# bicyclelab-charger-3.net
KiCad netlist of a schematic drawn in EAGLE
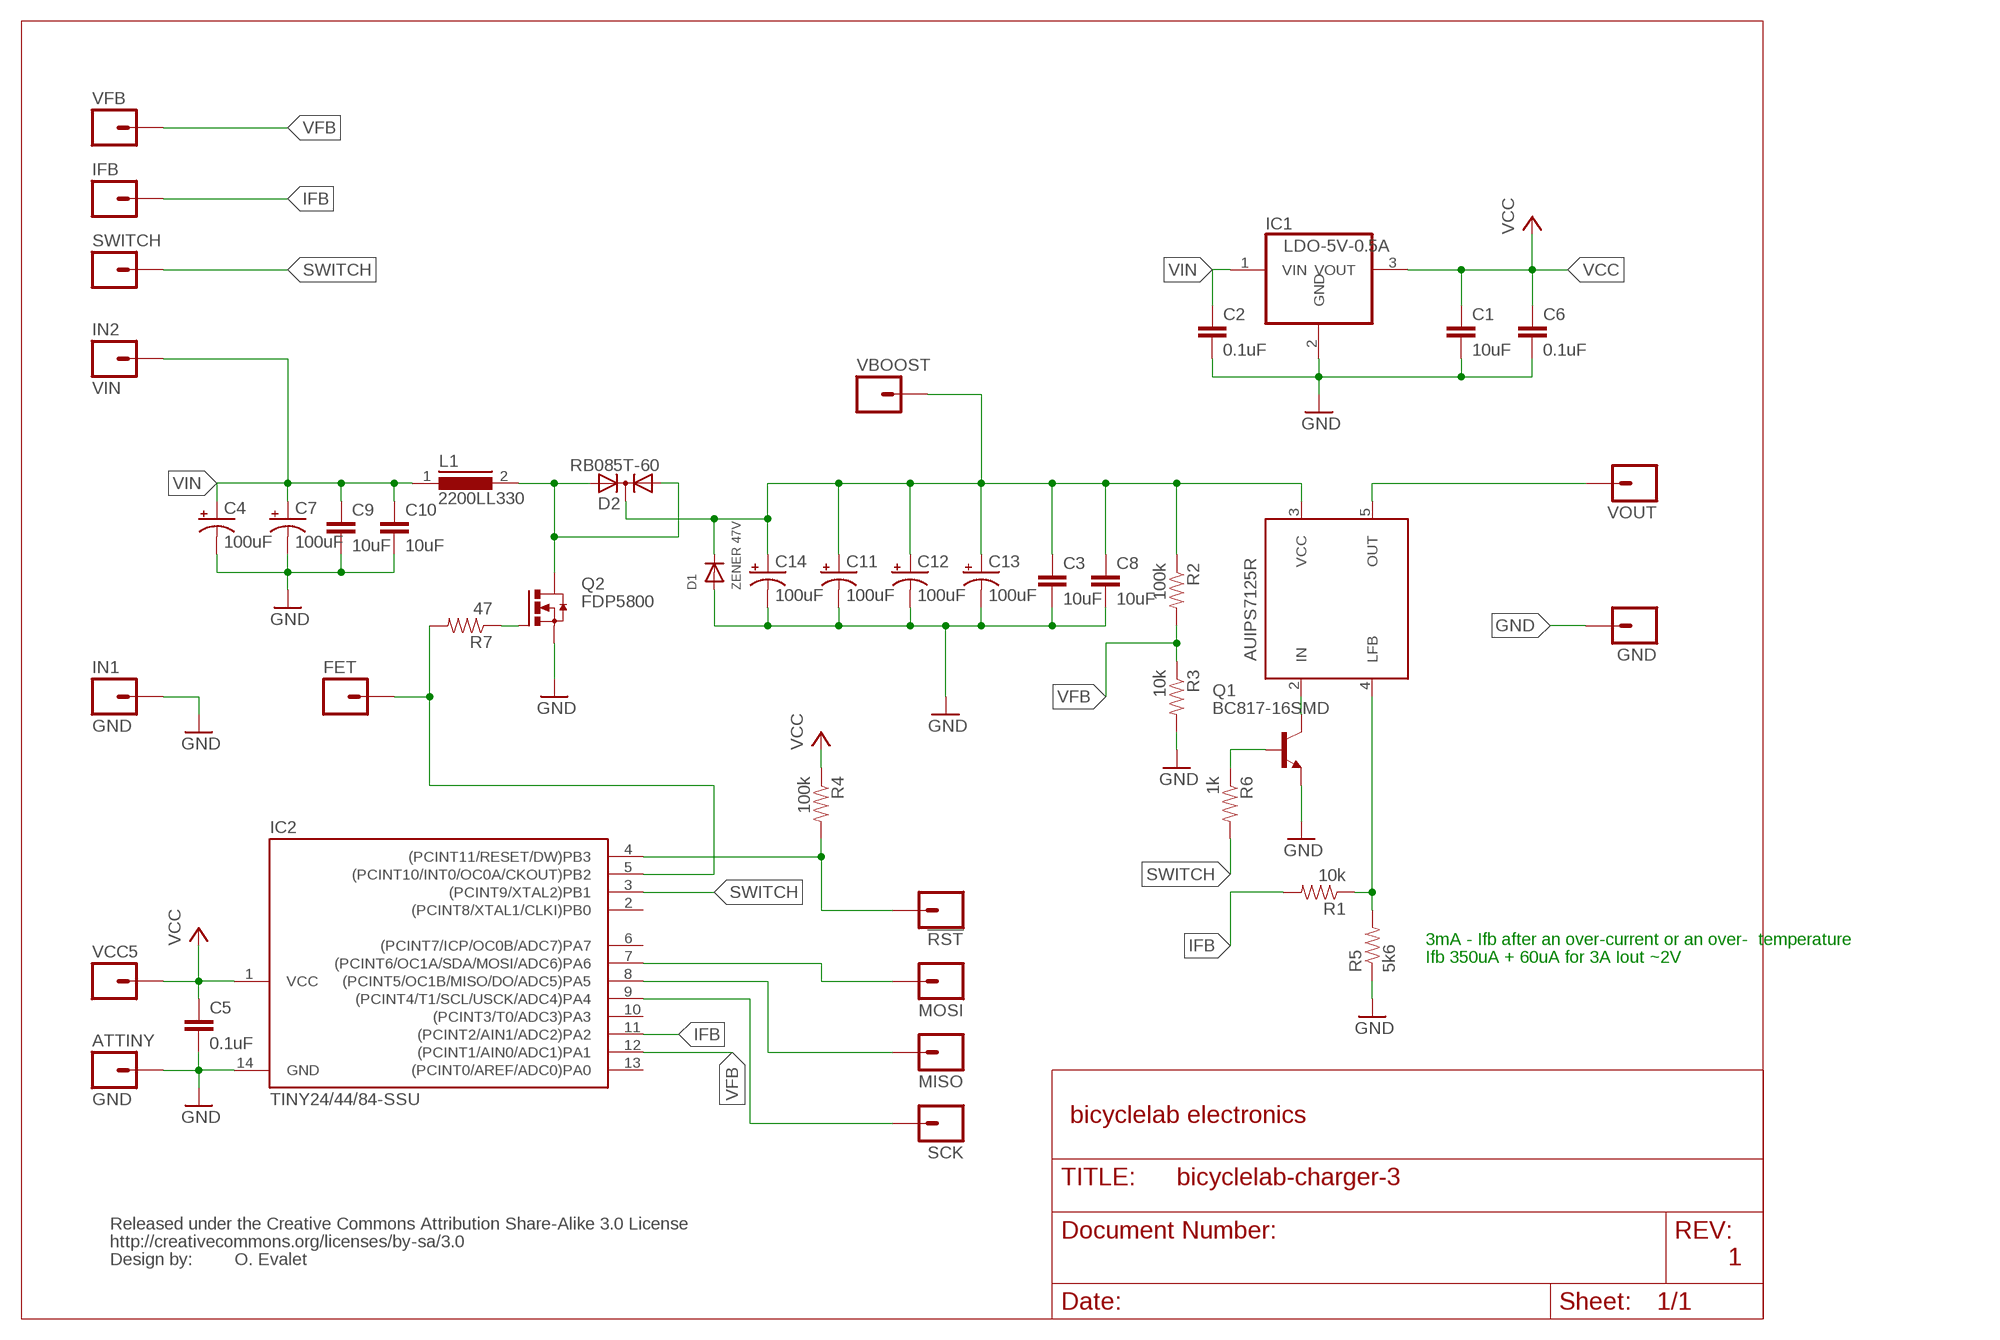
[diagram p0: schematic, sheet 1]

(export (version "E")
  (design (tool "Eeschema 10.0.6"))
  (components
    (comp (ref "!RST")
      (value "M01SMDNS")
      (footprint "eagle-import:1X01NS")
      (libsource (lib "eagle-import") (part "M01SMDNS"))
    )
    (comp (ref "ATTINY")
      (value "GND")
      (footprint "eagle-import:1X01NS")
      (libsource (lib "eagle-import") (part "M01SMDNS"))
    )
    (comp (ref "C1")
      (value "10uF")
      (footprint "eagle-import:1210")
      (libsource (lib "eagle-import") (part "CAP1210"))
    )
    (comp (ref "C2")
      (value "0.1uF")
      (footprint "eagle-import:0805")
      (libsource (lib "eagle-import") (part "CAP0805"))
    )
    (comp (ref "C3")
      (value "10uF")
      (footprint "eagle-import:1210")
      (libsource (lib "eagle-import") (part "CAP1210"))
    )
    (comp (ref "C4")
      (value "100uF")
      (footprint "eagle-import:PANASONIC_D")
      (libsource (lib "eagle-import") (part "CPOL-USD"))
    )
    (comp (ref "C5")
      (value "0.1uF")
      (footprint "eagle-import:0805")
      (libsource (lib "eagle-import") (part "CAP0805"))
    )
    (comp (ref "C6")
      (value "0.1uF")
      (footprint "eagle-import:0805")
      (libsource (lib "eagle-import") (part "CAP0805"))
    )
    (comp (ref "C7")
      (value "100uF")
      (footprint "eagle-import:PANASONIC_D")
      (libsource (lib "eagle-import") (part "CPOL-USD"))
    )
    (comp (ref "C8")
      (value "10uF")
      (footprint "eagle-import:1210")
      (libsource (lib "eagle-import") (part "CAP1210"))
    )
    (comp (ref "C9")
      (value "10uF")
      (footprint "eagle-import:1210")
      (libsource (lib "eagle-import") (part "CAP1210"))
    )
    (comp (ref "C10")
      (value "10uF")
      (footprint "eagle-import:1210")
      (libsource (lib "eagle-import") (part "CAP1210"))
    )
    (comp (ref "C11")
      (value "100uF")
      (footprint "eagle-import:PANASONIC_D")
      (libsource (lib "eagle-import") (part "CPOL-USD"))
    )
    (comp (ref "C12")
      (value "100uF")
      (footprint "eagle-import:PANASONIC_D")
      (libsource (lib "eagle-import") (part "CPOL-USD"))
    )
    (comp (ref "C13")
      (value "100uF")
      (footprint "eagle-import:PANASONIC_D")
      (libsource (lib "eagle-import") (part "CPOL-USD"))
    )
    (comp (ref "C14")
      (value "100uF")
      (footprint "eagle-import:PANASONIC_D")
      (libsource (lib "eagle-import") (part "CPOL-USD"))
    )
    (comp (ref "D1")
      (value "ZENER 47V")
      (footprint "eagle-import:SOD-123")
      (libsource (lib "eagle-import") (part "DIODESOD-123"))
    )
    (comp (ref "D2")
      (value "RB085T-60")
      (footprint "eagle-import:TO220AB")
      (libsource (lib "eagle-import") (part "DIODE-2AC|CATO220H"))
    )
    (comp (ref "FET")
      (value "M01SMDNS")
      (footprint "eagle-import:1X01NS")
      (libsource (lib "eagle-import") (part "M01SMDNS"))
    )
    (comp (ref "GND")
      (value "M01SMDNS")
      (footprint "eagle-import:1X01NS")
      (libsource (lib "eagle-import") (part "M01SMDNS"))
    )
    (comp (ref "IC1")
      (value "LDO-5V-0.5A")
      (footprint "eagle-import:SOT223")
      (libsource (lib "eagle-import") (part "LDO-5V-0.5A"))
    )
    (comp (ref "IC2")
      (value "TINY24/44/84-SSU")
      (footprint "eagle-import:SOIC14")
      (libsource (lib "eagle-import") (part "TINY24/44/84-SSU"))
    )
    (comp (ref "IFB")
      (value "M01SMDNS")
      (footprint "eagle-import:1X01NS")
      (libsource (lib "eagle-import") (part "M01SMDNS"))
    )
    (comp (ref "IN1")
      (value "GND")
      (footprint "eagle-import:1X01NS")
      (libsource (lib "eagle-import") (part "M01SMDNS"))
    )
    (comp (ref "IN2")
      (value "VIN")
      (footprint "eagle-import:1X01")
      (libsource (lib "eagle-import") (part "M01PTH"))
    )
    (comp (ref "L1")
      (value "2200LL330")
      (footprint "eagle-import:2200LL")
      (libsource (lib "eagle-import") (part "2200LL"))
    )
    (comp (ref "MISO")
      (value "M01SMDNS")
      (footprint "eagle-import:1X01NS")
      (libsource (lib "eagle-import") (part "M01SMDNS"))
    )
    (comp (ref "MOSI")
      (value "M01SMDNS")
      (footprint "eagle-import:1X01NS")
      (libsource (lib "eagle-import") (part "M01SMDNS"))
    )
    (comp (ref "Q1")
      (value "BC817-16SMD")
      (footprint "eagle-import:SOT23-BEC")
      (libsource (lib "eagle-import") (part "BC817SMD-16"))
    )
    (comp (ref "Q2")
      (value "FDP5800")
      (footprint "eagle-import:TO220AH")
      (libsource (lib "eagle-import") (part "IRF3704"))
    )
    (comp (ref "R1")
      (value "10k")
      (footprint "eagle-import:0805")
      (libsource (lib "eagle-import") (part "RESISTOR"))
    )
    (comp (ref "R2")
      (value "100k")
      (footprint "eagle-import:0805")
      (libsource (lib "eagle-import") (part "RESISTOR"))
    )
    (comp (ref "R3")
      (value "10k")
      (footprint "eagle-import:0805")
      (libsource (lib "eagle-import") (part "RESISTOR"))
    )
    (comp (ref "R4")
      (value "100k")
      (footprint "eagle-import:0805")
      (libsource (lib "eagle-import") (part "RESISTOR"))
    )
    (comp (ref "R5")
      (value "5k6")
      (footprint "eagle-import:0805")
      (libsource (lib "eagle-import") (part "RESISTOR"))
    )
    (comp (ref "R6")
      (value "1k")
      (footprint "eagle-import:0805")
      (libsource (lib "eagle-import") (part "RESISTOR"))
    )
    (comp (ref "R7")
      (value "47")
      (footprint "eagle-import:0805")
      (libsource (lib "eagle-import") (part "RESISTOR"))
    )
    (comp (ref "SCK")
      (value "M01SMDNS")
      (footprint "eagle-import:1X01NS")
      (libsource (lib "eagle-import") (part "M01SMDNS"))
    )
    (comp (ref "SWITCH")
      (value "M01SMDNS")
      (footprint "eagle-import:1X01NS")
      (libsource (lib "eagle-import") (part "M01SMDNS"))
    )
    (comp (ref "U$5")
      (value "CREATIVE_COMMONS")
      (footprint "eagle-import:CREATIVE_COMMONS")
      (libsource (lib "eagle-import") (part "CREATIVE_COMMONS"))
    )
    (comp (ref "U$8")
      (value "AUIPS7125R")
      (footprint "eagle-import:DPAK-5")
      (libsource (lib "eagle-import") (part "AUIPS7125R"))
    )
    (comp (ref "VBOOST")
      (value "M01SMDNS")
      (footprint "eagle-import:1X01NS")
      (libsource (lib "eagle-import") (part "M01SMDNS"))
    )
    (comp (ref "VCC5")
      (value "M01PTH")
      (footprint "eagle-import:1X01")
      (libsource (lib "eagle-import") (part "M01PTH"))
    )
    (comp (ref "VFB")
      (value "M01SMDNS")
      (footprint "eagle-import:1X01NS")
      (libsource (lib "eagle-import") (part "M01SMDNS"))
    )
    (comp (ref "VOUT")
      (value "M01PTH")
      (footprint "eagle-import:1X01")
      (libsource (lib "eagle-import") (part "M01PTH"))
    )
  )
  (nets
    (net (code "1") (name "GND") (class "Default")
      (node (ref "ATTINY") (pin "1") (pinfunction "1_1") (pintype "passive"))
      (node (ref "C1") (pin "2") (pinfunction "2_2") (pintype "passive"))
      (node (ref "C10") (pin "2") (pinfunction "2_2") (pintype "passive"))
      (node (ref "C11") (pin "-") (pinfunction "-_-") (pintype "passive"))
      (node (ref "C12") (pin "-") (pinfunction "-_-") (pintype "passive"))
      (node (ref "C13") (pin "-") (pinfunction "-_-") (pintype "passive"))
      (node (ref "C14") (pin "-") (pinfunction "-_-") (pintype "passive"))
      (node (ref "C2") (pin "2") (pinfunction "2_2") (pintype "passive"))
      (node (ref "C3") (pin "2") (pinfunction "2_2") (pintype "passive"))
      (node (ref "C4") (pin "-") (pinfunction "-_-") (pintype "passive"))
      (node (ref "C5") (pin "2") (pinfunction "2_2") (pintype "passive"))
      (node (ref "C6") (pin "2") (pinfunction "2_2") (pintype "passive"))
      (node (ref "C7") (pin "-") (pinfunction "-_-") (pintype "passive"))
      (node (ref "C8") (pin "2") (pinfunction "2_2") (pintype "passive"))
      (node (ref "C9") (pin "2") (pinfunction "2_2") (pintype "passive"))
      (node (ref "D1") (pin "A") (pinfunction "A_A") (pintype "passive"))
      (node (ref "GND") (pin "1") (pinfunction "1_1") (pintype "passive"))
      (node (ref "IC1") (pin "2") (pinfunction "GND_2") (pintype "power_in"))
      (node (ref "IC2") (pin "14") (pinfunction "GND_14") (pintype "power_in"))
      (node (ref "IN1") (pin "1") (pinfunction "1_1") (pintype "passive"))
      (node (ref "Q1") (pin "E") (pinfunction "E_E") (pintype "passive"))
      (node (ref "Q2") (pin "E") (pinfunction "S_E") (pintype "passive"))
      (node (ref "R3") (pin "2") (pinfunction "2_2") (pintype "passive"))
      (node (ref "R5") (pin "1") (pinfunction "1_1") (pintype "passive"))
    )
    (net (code "2") (name "IFB") (class "Default")
      (node (ref "IC2") (pin "11") (pinfunction "(PCINT2/AIN1/ADC2)PA2_11") (pintype "bidirectional"))
      (node (ref "IFB") (pin "1") (pinfunction "1_1") (pintype "passive"))
      (node (ref "R1") (pin "2") (pinfunction "2_2") (pintype "passive"))
    )
    (net (code "3") (name "Net-(IC2-(PCINT4{slash}T1{slash}SCL{slash}USCK{slash}ADC4)PA4)") (class "Default")
      (node (ref "IC2") (pin "9") (pinfunction "(PCINT4/T1/SCL/USCK/ADC4)PA4_9") (pintype "bidirectional"))
      (node (ref "SCK") (pin "1") (pinfunction "1_1") (pintype "passive"))
    )
    (net (code "4") (name "Net-(IC2-(PCINT5{slash}OC1B{slash}MISO{slash}DO{slash}ADC5)PA5)") (class "Default")
      (node (ref "IC2") (pin "8") (pinfunction "(PCINT5/OC1B/MISO/DO/ADC5)PA5_8") (pintype "bidirectional"))
      (node (ref "MISO") (pin "1") (pinfunction "1_1") (pintype "passive"))
    )
    (net (code "5") (name "Net-(IC2-(PCINT6{slash}OC1A{slash}SDA{slash}MOSI{slash}ADC6)PA6)") (class "Default")
      (node (ref "IC2") (pin "7") (pinfunction "(PCINT6/OC1A/SDA/MOSI/ADC6)PA6_7") (pintype "bidirectional"))
      (node (ref "MOSI") (pin "1") (pinfunction "1_1") (pintype "passive"))
    )
    (net (code "6") (name "Net-(IC2-(PCINT10{slash}INT0{slash}OC0A{slash}CKOUT)PB2)") (class "Default")
      (node (ref "FET") (pin "1") (pinfunction "1_1") (pintype "passive"))
      (node (ref "IC2") (pin "5") (pinfunction "(PCINT10/INT0/OC0A/CKOUT)PB2_5") (pintype "bidirectional"))
      (node (ref "R7") (pin "2") (pinfunction "2_2") (pintype "passive"))
    )
    (net (code "7") (name "Net-(IC2-(PCINT11{slash}RESET{slash}DW)PB3)") (class "Default")
      (node (ref "!RST") (pin "1") (pinfunction "1_1") (pintype "passive"))
      (node (ref "IC2") (pin "4") (pinfunction "(PCINT11/RESET/DW)PB3_4") (pintype "bidirectional"))
      (node (ref "R4") (pin "2") (pinfunction "2_2") (pintype "passive"))
    )
    (net (code "8") (name "Net-(Q1-PadB)") (class "Default")
      (node (ref "Q1") (pin "B") (pinfunction "B_B") (pintype "passive"))
      (node (ref "R6") (pin "1") (pinfunction "1_1") (pintype "passive"))
    )
    (net (code "9") (name "Net-(Q2-D)") (class "Default")
      (node (ref "D2") (pin "A1") (pinfunction "A1_A1") (pintype "passive"))
      (node (ref "D2") (pin "A2") (pinfunction "A2_A2") (pintype "passive"))
      (node (ref "L1") (pin "2") (pinfunction "2_2") (pintype "passive"))
      (node (ref "Q2") (pin "C") (pinfunction "D_C") (pintype "passive"))
    )
    (net (code "10") (name "Net-(Q2-G)") (class "Default")
      (node (ref "Q2") (pin "B") (pinfunction "G_B") (pintype "passive"))
      (node (ref "R7") (pin "1") (pinfunction "1_1") (pintype "passive"))
    )
    (net (code "11") (name "Net-(U$8-IN)") (class "Default")
      (node (ref "Q1") (pin "C") (pinfunction "C_C") (pintype "passive"))
      (node (ref "U$8") (pin "2") (pinfunction "IN_2") (pintype "input"))
    )
    (net (code "12") (name "Net-(U$8-LFB)") (class "Default")
      (node (ref "R1") (pin "1") (pinfunction "1_1") (pintype "passive"))
      (node (ref "R5") (pin "2") (pinfunction "2_2") (pintype "passive"))
      (node (ref "U$8") (pin "4") (pinfunction "LFB_4") (pintype "output"))
    )
    (net (code "13") (name "Net-(U$8-OUT)") (class "Default")
      (node (ref "U$8") (pin "5") (pinfunction "OUT_5") (pintype "output"))
      (node (ref "VOUT") (pin "1") (pinfunction "1_1") (pintype "passive"))
    )
    (net (code "14") (name "Net-(U$8-VCC)") (class "Default")
      (node (ref "C11") (pin "+") (pinfunction "+_+") (pintype "passive"))
      (node (ref "C12") (pin "+") (pinfunction "+_+") (pintype "passive"))
      (node (ref "C13") (pin "+") (pinfunction "+_+") (pintype "passive"))
      (node (ref "C14") (pin "+") (pinfunction "+_+") (pintype "passive"))
      (node (ref "C3") (pin "1") (pinfunction "1_1") (pintype "passive"))
      (node (ref "C8") (pin "1") (pinfunction "1_1") (pintype "passive"))
      (node (ref "D1") (pin "C") (pinfunction "C_C") (pintype "passive"))
      (node (ref "D2") (pin "C") (pinfunction "C_C") (pintype "passive"))
      (node (ref "R2") (pin "1") (pinfunction "1_1") (pintype "passive"))
      (node (ref "U$8") (pin "3") (pinfunction "VCC_3") (pintype "input"))
      (node (ref "VBOOST") (pin "1") (pinfunction "1_1") (pintype "passive"))
    )
    (net (code "15") (name "SWITCH") (class "Default")
      (node (ref "IC2") (pin "3") (pinfunction "(PCINT9/XTAL2)PB1_3") (pintype "bidirectional"))
      (node (ref "R6") (pin "2") (pinfunction "2_2") (pintype "passive"))
      (node (ref "SWITCH") (pin "1") (pinfunction "1_1") (pintype "passive"))
    )
    (net (code "16") (name "VCC") (class "Default")
      (node (ref "C1") (pin "1") (pinfunction "1_1") (pintype "passive"))
      (node (ref "C5") (pin "1") (pinfunction "1_1") (pintype "passive"))
      (node (ref "C6") (pin "1") (pinfunction "1_1") (pintype "passive"))
      (node (ref "IC1") (pin "3") (pinfunction "VOUT_3") (pintype "output"))
      (node (ref "IC2") (pin "1") (pinfunction "VCC_1") (pintype "power_in"))
      (node (ref "R4") (pin "1") (pinfunction "1_1") (pintype "passive"))
      (node (ref "VCC5") (pin "1") (pinfunction "1_1") (pintype "passive"))
    )
    (net (code "17") (name "VFB") (class "Default")
      (node (ref "IC2") (pin "12") (pinfunction "(PCINT1/AIN0/ADC1)PA1_12") (pintype "bidirectional"))
      (node (ref "R2") (pin "2") (pinfunction "2_2") (pintype "passive"))
      (node (ref "R3") (pin "1") (pinfunction "1_1") (pintype "passive"))
      (node (ref "VFB") (pin "1") (pinfunction "1_1") (pintype "passive"))
    )
    (net (code "18") (name "VIN") (class "Default")
      (node (ref "C10") (pin "1") (pinfunction "1_1") (pintype "passive"))
      (node (ref "C2") (pin "1") (pinfunction "1_1") (pintype "passive"))
      (node (ref "C4") (pin "+") (pinfunction "+_+") (pintype "passive"))
      (node (ref "C7") (pin "+") (pinfunction "+_+") (pintype "passive"))
      (node (ref "C9") (pin "1") (pinfunction "1_1") (pintype "passive"))
      (node (ref "IC1") (pin "1") (pinfunction "VIN_1") (pintype "input"))
      (node (ref "IN2") (pin "1") (pinfunction "1_1") (pintype "passive"))
      (node (ref "L1") (pin "1") (pinfunction "1_1") (pintype "passive"))
    )
    (net (code "19") (name "unconnected-(IC2-(PCINT0{slash}AREF{slash}ADC0)PA0-Pad13)") (class "Default")
      (node (ref "IC2") (pin "13") (pinfunction "(PCINT0/AREF/ADC0)PA0_13") (pintype "bidirectional"))
    )
    (net (code "20") (name "unconnected-(IC2-(PCINT3{slash}T0{slash}ADC3)PA3-Pad10)") (class "Default")
      (node (ref "IC2") (pin "10") (pinfunction "(PCINT3/T0/ADC3)PA3_10") (pintype "bidirectional"))
    )
    (net (code "21") (name "unconnected-(IC2-(PCINT7{slash}ICP{slash}OC0B{slash}ADC7)PA7-Pad6)") (class "Default")
      (node (ref "IC2") (pin "6") (pinfunction "(PCINT7/ICP/OC0B/ADC7)PA7_6") (pintype "bidirectional"))
    )
    (net (code "22") (name "unconnected-(IC2-(PCINT8{slash}XTAL1{slash}CLKI)PB0-Pad2)") (class "Default")
      (node (ref "IC2") (pin "2") (pinfunction "(PCINT8/XTAL1/CLKI)PB0_2") (pintype "bidirectional"))
    )
    (net (code "23") (name "unconnected-(U$8-NC-Pad1)") (class "Default")
      (node (ref "U$8") (pin "1") (pinfunction "NC_1") (pintype "no_connect"))
    )
  )
)
